# FLIP_FLOP.net
KiCad netlist of a schematic drawn in Altium Designer
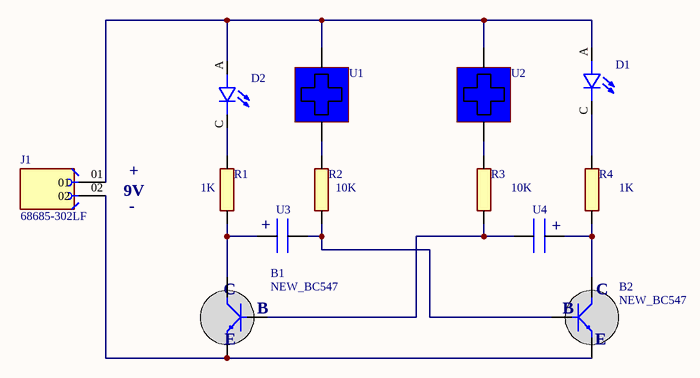
[diagram p0: FLIP_FLOP.SchDoc]

(export (version "E")
  (design (tool "Eeschema 10.0.6"))
  (components
    (comp (ref "B1")
      (value "NEW_BC547")
      (footprint "NEW_BC547")
      (description "BC547")
      (libsource (lib "NEW_BC547") (part "NEW_BC547"))
    )
    (comp (ref "B2")
      (value "NEW_BC547")
      (footprint "NEW_BC547")
      (description "BC547")
      (libsource (lib "NEW_BC547") (part "NEW_BC547"))
    )
    (comp (ref "D1")
      (value "L08R5000Q1")
      (footprint "LEDRD254W57D500H1070")
      (fields (field (name "MF") "LED Technology"))
      (libsource (lib "YELLOW_LED") (part "L08R5000Q1"))
    )
    (comp (ref "D2")
      (value "L08R5000Q1")
      (footprint "LEDRD254W57D500H1070")
      (fields (field (name "MF") "LED Technology"))
      (libsource (lib "YELLOW_LED") (part "L08R5000Q1"))
    )
    (comp (ref "J1")
      (value "68685-302LF")
      (footprint "AMPHENOL_68685-302LF")
      (fields
        (field (name "DIGI-KEY_PART_NUMBER") "609-68685-302LF-ND")
        (field (name "MF") "Amphenol ICC (FCI)")
      )
      (libsource (lib "2pin_connector") (part "68685-302LF"))
    )
    (comp (ref "R1")
      (value "VERTICAL RESISTOR")
      (footprint "VERTICAL_RESISTOR")
      (libsource (lib "VERTICAL") (part "VERTICAL RESISTOR"))
    )
    (comp (ref "R2")
      (value "VERTICAL RESISTOR")
      (footprint "VERTICAL_RESISTOR")
      (libsource (lib "VERTICAL") (part "VERTICAL RESISTOR"))
    )
    (comp (ref "R3")
      (value "VERTICAL RESISTOR")
      (footprint "VERTICAL_RESISTOR")
      (libsource (lib "VERTICAL") (part "VERTICAL RESISTOR"))
    )
    (comp (ref "R4")
      (value "VERTICAL RESISTOR")
      (footprint "VERTICAL_RESISTOR")
      (libsource (lib "VERTICAL") (part "VERTICAL RESISTOR"))
    )
    (comp (ref "U1")
      (value "220K TRIMPOT")
      (footprint "220K_TRIMPOT")
      (description "vertical trimpot")
      (libsource (lib "220K_TRIMPOT") (part "220K TRIMPOT"))
    )
    (comp (ref "U2")
      (value "220K TRIMPOT")
      (footprint "220K_TRIMPOT")
      (description "vertical trimpot")
      (libsource (lib "220K_TRIMPOT") (part "220K TRIMPOT"))
    )
    (comp (ref "U3")
      (value "10uF CAPACITOR")
      (footprint "10uF_CAPACITOR")
      (libsource (lib "10uF_CAPACITOR") (part "10uF CAPACITOR"))
    )
    (comp (ref "U4")
      (value "10uF CAPACITOR")
      (footprint "10uF_CAPACITOR")
      (libsource (lib "10uF_CAPACITOR") (part "10uF CAPACITOR"))
    )
  )
  (nets
    (net (code "1") (name "Net-(B1-Pad0)") (class "Default")
      (node (ref "B1") (pin "0") (pinfunction "0_0") (pintype "passive"))
      (node (ref "R1") (pin "0") (pinfunction "0_0") (pintype "passive"))
      (node (ref "U3") (pin "0") (pinfunction "0_0") (pintype "passive"))
    )
    (net (code "2") (name "Net-(B1-Pad1)") (class "Default")
      (node (ref "B1") (pin "1") (pinfunction "1_1") (pintype "passive"))
      (node (ref "R3") (pin "0") (pinfunction "0_0") (pintype "passive"))
      (node (ref "U4") (pin "0") (pinfunction "0_0") (pintype "passive"))
    )
    (net (code "3") (name "Net-(B1-Pad2)") (class "Default")
      (node (ref "B1") (pin "2") (pinfunction "2_2") (pintype "passive"))
      (node (ref "B2") (pin "2") (pinfunction "2_2") (pintype "passive"))
      (node (ref "J1") (pin "02") (pinfunction "02_02") (pintype "passive"))
    )
    (net (code "4") (name "Net-(B2-Pad0)") (class "Default")
      (node (ref "B2") (pin "0") (pinfunction "0_0") (pintype "passive"))
      (node (ref "R4") (pin "0") (pinfunction "0_0") (pintype "passive"))
      (node (ref "U4") (pin "1") (pinfunction "1_1") (pintype "passive"))
    )
    (net (code "5") (name "Net-(B2-Pad1)") (class "Default")
      (node (ref "B2") (pin "1") (pinfunction "1_1") (pintype "passive"))
      (node (ref "R2") (pin "0") (pinfunction "0_0") (pintype "passive"))
      (node (ref "U3") (pin "1") (pinfunction "1_1") (pintype "passive"))
    )
    (net (code "6") (name "Net-(D1-PadA)") (class "Default")
      (node (ref "D1") (pin "A") (pinfunction "A_A") (pintype "passive"))
      (node (ref "D2") (pin "A") (pinfunction "A_A") (pintype "passive"))
      (node (ref "J1") (pin "01") (pinfunction "01_01") (pintype "passive"))
      (node (ref "U1") (pin "1") (pinfunction "1_1") (pintype "passive"))
      (node (ref "U2") (pin "1") (pinfunction "1_1") (pintype "passive"))
    )
    (net (code "7") (name "Net-(D1-PadC)") (class "Default")
      (node (ref "D1") (pin "C") (pinfunction "C_C") (pintype "passive"))
      (node (ref "R4") (pin "1") (pinfunction "1_1") (pintype "passive"))
    )
    (net (code "8") (name "Net-(D2-PadC)") (class "Default")
      (node (ref "D2") (pin "C") (pinfunction "C_C") (pintype "passive"))
      (node (ref "R1") (pin "1") (pinfunction "1_1") (pintype "passive"))
    )
    (net (code "9") (name "Net-(R2-Pad1)") (class "Default")
      (node (ref "R2") (pin "1") (pinfunction "1_1") (pintype "passive"))
      (node (ref "U1") (pin "0") (pinfunction "0_0") (pintype "passive"))
    )
    (net (code "10") (name "Net-(R3-Pad1)") (class "Default")
      (node (ref "R3") (pin "1") (pinfunction "1_1") (pintype "passive"))
      (node (ref "U2") (pin "0") (pinfunction "0_0") (pintype "passive"))
    )
  )
)
